# BMS_Schematic.net
KiCad netlist of a schematic drawn in Altium Designer
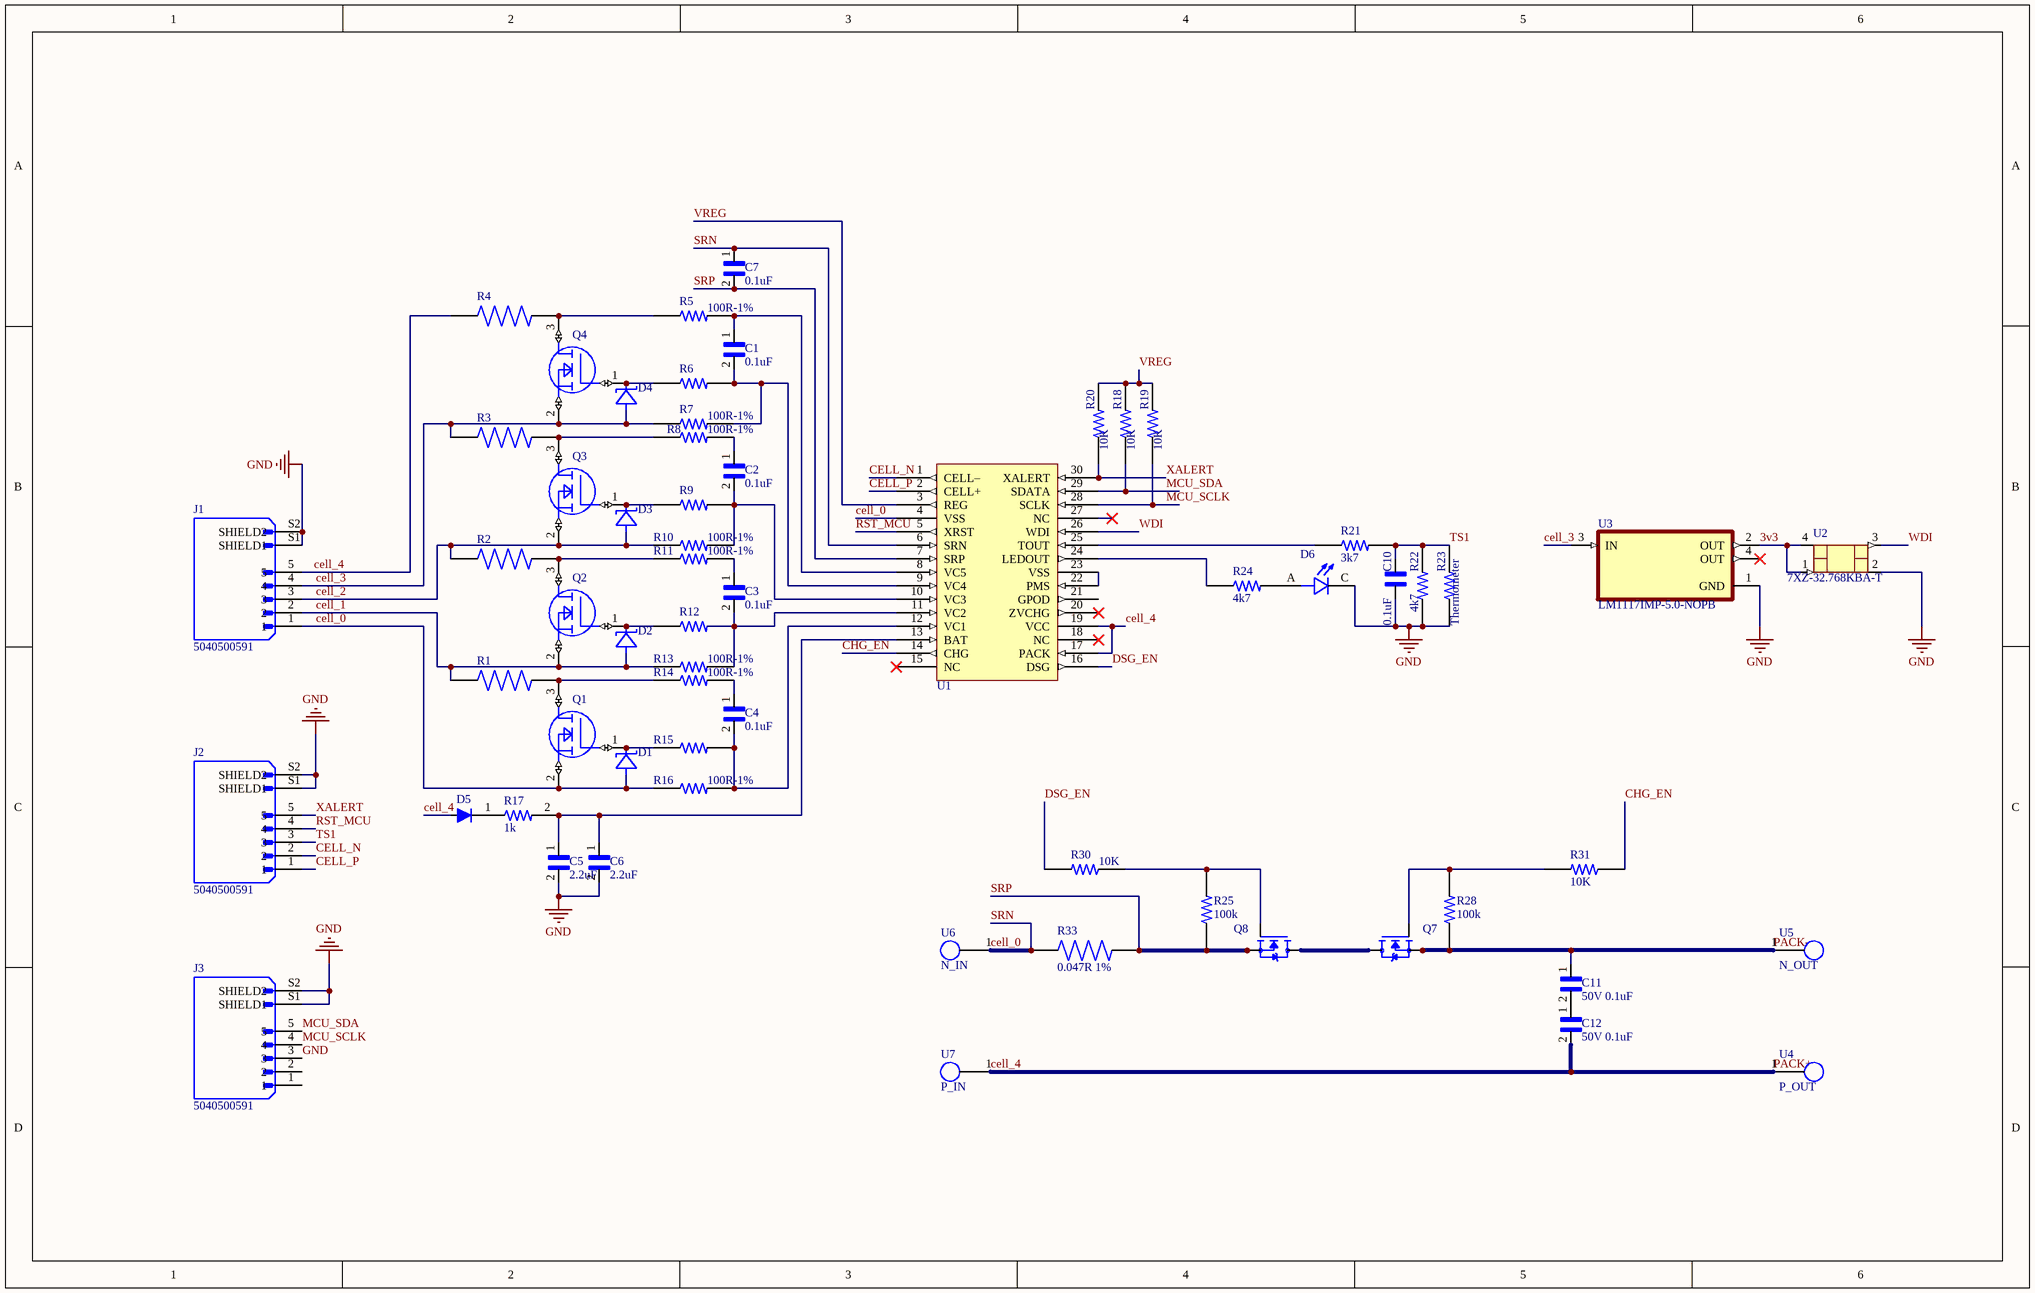
[diagram p0: BMS_Schematic.SchDoc]

(export (version "E")
  (design (tool "Eeschema 10.0.6"))
  (components
    (comp (ref "C1")
      (value "0.1uF")
      (footprint "cap_0603:CAPC1608X90")
      (description "CAP CER SMD")
      (fields (field (name "MP") "LD035C181JAB2A") (field (name "MF") "AVX"))
      (libsource (lib "cap_0603") (part "LD035C181JAB2A"))
    )
    (comp (ref "C2")
      (value "0.1uF")
      (footprint "CAPC1608X90")
      (description "CAP CER SMD")
      (fields (field (name "MP") "LD035C181JAB2A") (field (name "MF") "AVX"))
      (libsource (lib "LD035C181JAB2A") (part "LD035C181JAB2A"))
    )
    (comp (ref "C3")
      (value "0.1uF")
      (footprint "CAPC1608X90")
      (description "CAP CER SMD")
      (fields (field (name "MP") "LD035C181JAB2A") (field (name "MF") "AVX"))
      (libsource (lib "LD035C181JAB2A") (part "LD035C181JAB2A"))
    )
    (comp (ref "C4")
      (value "0.1uF")
      (footprint "CAPC1608X90")
      (description "CAP CER SMD")
      (fields (field (name "MP") "LD035C181JAB2A") (field (name "MF") "AVX"))
      (libsource (lib "LD035C181JAB2A") (part "LD035C181JAB2A"))
    )
    (comp (ref "C5")
      (value "2.2uF")
      (footprint "CAPC1608X90")
      (description "CAP CER SMD")
      (fields (field (name "MP") "LD035C181JAB2A") (field (name "MF") "AVX"))
      (libsource (lib "LD035C181JAB2A") (part "LD035C181JAB2A"))
    )
    (comp (ref "C6")
      (value "2.2uF")
      (footprint "CAPC1608X90")
      (description "CAP CER SMD")
      (fields (field (name "MP") "LD035C181JAB2A") (field (name "MF") "AVX"))
      (libsource (lib "LD035C181JAB2A") (part "LD035C181JAB2A"))
    )
    (comp (ref "C7")
      (value "0.1uF")
      (footprint "CAPC1608X90")
      (description "CAP CER SMD")
      (fields (field (name "MP") "LD035C181JAB2A") (field (name "MF") "AVX"))
      (libsource (lib "LD035C181JAB2A") (part "LD035C181JAB2A"))
    )
    (comp (ref "C10")
      (value "0.1uF")
      (footprint "CAPC1608X90")
      (description "CAP CER SMD")
      (fields (field (name "MP") "LD035C181JAB2A") (field (name "MF") "AVX"))
      (libsource (lib "") (part "LD035C181JAB2A_1"))
    )
    (comp (ref "C11")
      (value "50V 0.1uF")
      (footprint "CAPC1608X90")
      (description "CAP CER SMD")
      (fields (field (name "MP") "LD035C181JAB2A") (field (name "MF") "AVX"))
      (libsource (lib "LD035C181JAB2A") (part "LD035C181JAB2A"))
    )
    (comp (ref "C12")
      (value "50V 0.1uF")
      (footprint "CAPC1608X90")
      (description "CAP CER SMD")
      (fields (field (name "MP") "LD035C181JAB2A") (field (name "MF") "AVX"))
      (libsource (lib "LD035C181JAB2A") (part "LD035C181JAB2A"))
    )
    (comp (ref "D1")
      (value "MMSZ5232B+")
      (footprint "SOD123:SOD123")
      (description "Zener Diode 5.6V 500mW Â±5% Surface Mount SOD-123")
      (fields (field (name "MP") "MMSZ5232B") (field (name "MF") "ON Semiconductor"))
      (libsource (lib "MMSZ5232B+") (part "MMSZ5232B+"))
    )
    (comp (ref "D2")
      (value "MMSZ5232B+")
      (footprint "SOD123:SOD123")
      (description "Zener Diode 5.6V 500mW Â±5% Surface Mount SOD-123")
      (fields (field (name "MP") "MMSZ5232B") (field (name "MF") "ON Semiconductor"))
      (libsource (lib "MMSZ5232B+") (part "MMSZ5232B+"))
    )
    (comp (ref "D3")
      (value "MMSZ5232B+")
      (footprint "SOD123:SOD123")
      (description "Zener Diode 5.6V 500mW Â±5% Surface Mount SOD-123")
      (fields (field (name "MP") "MMSZ5232B") (field (name "MF") "ON Semiconductor"))
      (libsource (lib "MMSZ5232B+") (part "MMSZ5232B+"))
    )
    (comp (ref "D4")
      (value "MMSZ5232B+")
      (footprint "SOD123:SOD123")
      (description "Zener Diode 5.6V 500mW Â±5% Surface Mount SOD-123")
      (fields (field (name "MP") "MMSZ5232B") (field (name "MF") "ON Semiconductor"))
      (libsource (lib "MMSZ5232B+") (part "MMSZ5232B+"))
    )
    (comp (ref "D5")
      (value "MMSD4148T1G")
      (footprint "SnapEDApcb:SOD123")
      (description "DIODE GEN PURP 100V 200MA SOD123")
      (fields (field (name "MF") "ON Semiconductor") (field (name "MP") "MBR0520L"))
      (libsource (lib "SnapEDAsch") (part "MMSD4148T1G"))
    )
    (comp (ref "D6")
      (value "SML-D12U1WT86")
      (footprint "led_0603:LED_SML-D12Y1WT86")
      (description "Red 620nm LED Indication - Discrete 2.2V 0603 _1608 Metric_")
      (fields (field (name "MF") "Rohm"))
      (libsource (lib "led_0603") (part "SML-D12U1WT86"))
    )
    (comp (ref "J1")
      (value "5040500591")
      (footprint "MOLEX_5040500591:MOLEX_5040500591")
      (description "Connector Header Surface Mount, Right Angle 5 position 0.059 (1.50mm)")
      (fields (field (name "MF") "Molex"))
      (libsource (lib "5040500591") (part "5040500591"))
    )
    (comp (ref "J2")
      (value "5040500591")
      (footprint "MOLEX_5040500591:MOLEX_5040500591")
      (description "Connector Header Surface Mount, Right Angle 5 position 0.059 (1.50mm)")
      (fields (field (name "MF") "Molex"))
      (libsource (lib "5040500591") (part "5040500591"))
    )
    (comp (ref "J3")
      (value "5040500591")
      (footprint "MOLEX_5040500591:MOLEX_5040500591")
      (description "Connector Header Surface Mount, Right Angle 5 position 0.059 (1.50mm)")
      (fields (field (name "MF") "Molex"))
      (libsource (lib "5040500591") (part "5040500591"))
    )
    (comp (ref "Q1")
      (value "DMG2302UK-7")
      (footprint "SOT91P240X105-3N")
      (description "N-Channel 20 V 2.8A (Ta) 660mW (Ta) Surface Mount SOT-23-3")
      (fields (field (name "MF") "Diodes Inc."))
      (libsource (lib "DMG2302UK-7") (part "DMG2302UK-7"))
    )
    (comp (ref "Q2")
      (value "DMG2302UK-7")
      (footprint "SOT91P240X105-3N")
      (description "N-Channel 20 V 2.8A (Ta) 660mW (Ta) Surface Mount SOT-23-3")
      (fields (field (name "MF") "Diodes Inc."))
      (libsource (lib "DMG2302UK-7") (part "DMG2302UK-7"))
    )
    (comp (ref "Q3")
      (value "DMG2302UK-7")
      (footprint "SOT91P240X105-3N")
      (description "N-Channel 20 V 2.8A (Ta) 660mW (Ta) Surface Mount SOT-23-3")
      (fields (field (name "MF") "Diodes Inc."))
      (libsource (lib "DMG2302UK-7") (part "DMG2302UK-7"))
    )
    (comp (ref "Q4")
      (value "DMG2302UK-7")
      (footprint "SOT91P240X105-3N")
      (description "N-Channel 20 V 2.8A (Ta) 660mW (Ta) Surface Mount SOT-23-3")
      (fields (field (name "MF") "Diodes Inc."))
      (libsource (lib "DMG2302UK-7") (part "DMG2302UK-7"))
    )
    (comp (ref "Q7")
      (value "IPT60R028G7XTMA1")
      (footprint "MOSFET_8HSOF:TRANS_IPT60R028G7XTMA1")
      (fields
        (field (name "MF") "Infineon Technologies")
        (field (name "DIGI-KEY_PART_NUMBER") "IPT60R028G7XTMA1CT-ND")
      )
      (libsource (lib "MOSFET_8HSOF") (part "IPT60R028G7XTMA1"))
    )
    (comp (ref "Q8")
      (value "IPT60R028G7XTMA1")
      (footprint "MOSFET_8HSOF:TRANS_IPT60R028G7XTMA1")
      (fields
        (field (name "MF") "Infineon Technologies")
        (field (name "DIGI-KEY_PART_NUMBER") "IPT60R028G7XTMA1CT-ND")
      )
      (libsource (lib "MOSFET_8HSOF") (part "IPT60R028G7XTMA1"))
    )
    (comp (ref "R1")
      (value "ERJS1TJ561U")
      (footprint "RES_ERJS1TJ561U:RES_ERJS1TJ561U")
      (libsource (lib "ERJS1TJ561U") (part "ERJS1TJ561U"))
    )
    (comp (ref "R2")
      (value "ERJS1TJ561U")
      (footprint "RES_ERJS1TJ561U:RES_ERJS1TJ561U")
      (libsource (lib "ERJS1TJ561U") (part "ERJS1TJ561U"))
    )
    (comp (ref "R3")
      (value "ERJS1TJ561U")
      (footprint "RES_ERJS1TJ561U:RES_ERJS1TJ561U")
      (libsource (lib "ERJS1TJ561U") (part "ERJS1TJ561U"))
    )
    (comp (ref "R4")
      (value "ERJS1TJ561U")
      (footprint "RES_ERJS1TJ561U:RES_ERJS1TJ561U")
      (libsource (lib "ERJS1TJ561U") (part "ERJS1TJ561U"))
    )
    (comp (ref "R5")
      (value "100R-1%")
      (footprint "RESC1608X50N:RESC1608X50N")
      (description "CPF 0603 10K 0.1% 25PPM 1K RL")
      (fields (field (name "MP") "8-1676481-6"))
      (libsource (lib "8-1676481-6") (part "8-1676481-6"))
    )
    (comp (ref "R6")
      (value "8-1676481-6")
      (footprint "RESC1608X50N:RESC1608X50N")
      (description "CPF 0603 10K 0.1% 25PPM 1K RL")
      (libsource (lib "8-1676481-6") (part "8-1676481-6"))
    )
    (comp (ref "R7")
      (value "100R-1%")
      (footprint "RESC1608X50N:RESC1608X50N")
      (description "CPF 0603 10K 0.1% 25PPM 1K RL")
      (fields (field (name "MP") "8-1676481-6"))
      (libsource (lib "8-1676481-6") (part "8-1676481-6"))
    )
    (comp (ref "R8")
      (value "100R-1%")
      (footprint "RESC1608X50N:RESC1608X50N")
      (description "CPF 0603 10K 0.1% 25PPM 1K RL")
      (fields (field (name "MP") "8-1676481-6"))
      (libsource (lib "8-1676481-6") (part "8-1676481-6"))
    )
    (comp (ref "R9")
      (value "8-1676481-6")
      (footprint "RESC1608X50N:RESC1608X50N")
      (description "CPF 0603 10K 0.1% 25PPM 1K RL")
      (libsource (lib "8-1676481-6") (part "8-1676481-6"))
    )
    (comp (ref "R10")
      (value "100R-1%")
      (footprint "RESC1608X50N:RESC1608X50N")
      (description "CPF 0603 10K 0.1% 25PPM 1K RL")
      (fields (field (name "MP") "8-1676481-6"))
      (libsource (lib "8-1676481-6") (part "8-1676481-6"))
    )
    (comp (ref "R11")
      (value "100R-1%")
      (footprint "RESC1608X50N:RESC1608X50N")
      (description "CPF 0603 10K 0.1% 25PPM 1K RL")
      (fields (field (name "MP") "8-1676481-6"))
      (libsource (lib "8-1676481-6") (part "8-1676481-6"))
    )
    (comp (ref "R12")
      (value "8-1676481-6")
      (footprint "RESC1608X50N:RESC1608X50N")
      (description "CPF 0603 10K 0.1% 25PPM 1K RL")
      (libsource (lib "8-1676481-6") (part "8-1676481-6"))
    )
    (comp (ref "R13")
      (value "100R-1%")
      (footprint "RESC1608X50N:RESC1608X50N")
      (description "CPF 0603 10K 0.1% 25PPM 1K RL")
      (fields (field (name "MP") "8-1676481-6"))
      (libsource (lib "8-1676481-6") (part "8-1676481-6"))
    )
    (comp (ref "R14")
      (value "100R-1%")
      (footprint "RESC1608X50N:RESC1608X50N")
      (description "CPF 0603 10K 0.1% 25PPM 1K RL")
      (fields (field (name "MP") "8-1676481-6"))
      (libsource (lib "8-1676481-6") (part "8-1676481-6"))
    )
    (comp (ref "R15")
      (value "8-1676481-6")
      (footprint "RESC1608X50N:RESC1608X50N")
      (description "CPF 0603 10K 0.1% 25PPM 1K RL")
      (libsource (lib "8-1676481-6") (part "8-1676481-6"))
    )
    (comp (ref "R16")
      (value "100R-1%")
      (footprint "RESC1608X50N:RESC1608X50N")
      (description "CPF 0603 10K 0.1% 25PPM 1K RL")
      (fields (field (name "MP") "8-1676481-6"))
      (libsource (lib "8-1676481-6") (part "8-1676481-6"))
    )
    (comp (ref "R17")
      (value "1k")
      (footprint "RESC1608X50N")
      (description "CPF 0603 30K 0.1% 25PPM 1K RL")
      (fields (field (name "MP") "8-1676481-6"))
      (libsource (lib "") (part "8-1676481-6_1"))
    )
    (comp (ref "R18")
      (value "10K")
      (footprint "RESC1608X50N:RESC1608X50N")
      (description "CPF 0603 10K 0.1% 25PPM 1K RL")
      (fields (field (name "MP") "8-1676481-6"))
      (libsource (lib "8-1676481-6") (part "8-1676481-6"))
    )
    (comp (ref "R19")
      (value "10K")
      (footprint "RESC1608X50N:RESC1608X50N")
      (description "CPF 0603 10K 0.1% 25PPM 1K RL")
      (fields (field (name "MP") "8-1676481-6"))
      (libsource (lib "8-1676481-6") (part "8-1676481-6"))
    )
    (comp (ref "R20")
      (value "10K")
      (footprint "RESC1608X50N:RESC1608X50N")
      (description "CPF 0603 10K 0.1% 25PPM 1K RL")
      (fields (field (name "MP") "8-1676481-6"))
      (libsource (lib "8-1676481-6") (part "8-1676481-6"))
    )
    (comp (ref "R21")
      (value "3k7")
      (footprint "RESC1608X50N:RESC1608X50N")
      (description "CPF 0603 10K 0.1% 25PPM 1K RL")
      (fields (field (name "MP") "8-1676481-6"))
      (libsource (lib "8-1676481-6") (part "8-1676481-6"))
    )
    (comp (ref "R22")
      (value "4k7")
      (footprint "RESC1608X50N:RESC1608X50N")
      (description "CPF 0603 10K 0.1% 25PPM 1K RL")
      (fields (field (name "MP") "8-1676481-6"))
      (libsource (lib "8-1676481-6") (part "8-1676481-6"))
    )
    (comp (ref "R23")
      (value "Thermometer")
      (footprint "RESC1608X50N:RESC1608X50N")
      (description "CPF 0603 10K 0.1% 25PPM 1K RL")
      (fields (field (name "MP") "8-1676481-6"))
      (libsource (lib "8-1676481-6") (part "8-1676481-6"))
    )
    (comp (ref "R24")
      (value "4k7")
      (footprint "RESC1608X50N:RESC1608X50N")
      (description "CPF 0603 10K 0.1% 25PPM 1K RL")
      (fields (field (name "MP") "8-1676481-6"))
      (libsource (lib "8-1676481-6") (part "8-1676481-6"))
    )
    (comp (ref "R25")
      (value "100k")
      (footprint "RESC1608X50N:RESC1608X50N")
      (description "CPF 0603 10K 0.1% 25PPM 1K RL")
      (fields (field (name "MP") "8-1676481-6"))
      (libsource (lib "8-1676481-6") (part "8-1676481-6"))
    )
    (comp (ref "R28")
      (value "100k")
      (footprint "RESC1608X50N:RESC1608X50N")
      (description "CPF 0603 10K 0.1% 25PPM 1K RL")
      (fields (field (name "MP") "8-1676481-6"))
      (libsource (lib "8-1676481-6") (part "8-1676481-6"))
    )
    (comp (ref "R30")
      (value "10K")
      (footprint "RESC1608X50N:RESC1608X50N")
      (description "CPF 0603 10K 0.1% 25PPM 1K RL")
      (fields (field (name "MP") "8-1676481-6"))
      (libsource (lib "8-1676481-6") (part "8-1676481-6"))
    )
    (comp (ref "R31")
      (value "10K")
      (footprint "RESC1608X50N:RESC1608X50N")
      (description "CPF 0603 10K 0.1% 25PPM 1K RL")
      (fields (field (name "MP") "8-1676481-6"))
      (libsource (lib "8-1676481-6") (part "8-1676481-6"))
    )
    (comp (ref "R33")
      (value "0.047R 1%")
      (footprint "RES_ERJS1TJ561U:RES_ERJS1TJ561U")
      (fields (field (name "MP") "ERJS1TJ561U"))
      (libsource (lib "ERJS1TJ561U") (part "ERJS1TJ561U"))
    )
    (comp (ref "U1")
      (value "BQ29330")
      (footprint "SOP50P640X120-30N")
      (libsource (lib "BQ29330DBT") (part "BQ29330"))
    )
    (comp (ref "U2")
      (value "7XZ-32.768KBA-T")
      (footprint "oscillator:OSCCILATOR")
      (description "Oscillator 32.768 Khz")
      (libsource (lib "oscillator") (part "7XZ-32.768KBA-T"))
    )
    (comp (ref "U3")
      (value "LM1117IMP-5.0-NOPB")
      (footprint "SOT230P700X180-4N:SOT230P700X180-4N")
      (fields (field (name "MF") "Texas Instruments") (field (name "MP") "LM1117IMP50"))
      (libsource (lib "LM1117IMP-5.0-NOPB") (part "LM1117IMP-5.0-NOPB"))
    )
    (comp (ref "U4")
      (value "P_OUT")
      (footprint "battery_socket:PCBComponent_1")
      (description "Soldering part")
      (libsource (lib "battery_socket") (part "battery_socket"))
    )
    (comp (ref "U5")
      (value "N_OUT")
      (footprint "battery_socket:PCBComponent_1")
      (description "Soldering part")
      (libsource (lib "battery_socket") (part "battery_socket"))
    )
    (comp (ref "U6")
      (value "N_IN")
      (footprint "battery_socket:PCBComponent_1")
      (description "Soldering part")
      (libsource (lib "battery_socket") (part "battery_socket"))
    )
    (comp (ref "U7")
      (value "P_IN")
      (footprint "battery_socket:PCBComponent_1")
      (description "Soldering part")
      (libsource (lib "battery_socket") (part "battery_socket"))
    )
  )
  (nets
    (net (code "1") (name "/3v3") (class "Default")
      (node (ref "U2") (pin "1") (pinfunction "ENA_1") (pintype "input"))
      (node (ref "U2") (pin "4") (pinfunction "VDD_4") (pintype "power_in"))
      (node (ref "U3") (pin "2") (pinfunction "OUT_2") (pintype "output"))
    )
    (net (code "2") (name "/CELL_N") (class "Default")
      (node (ref "J2") (pin "2") (pinfunction "2_2") (pintype "passive"))
      (node (ref "U1") (pin "1") (pinfunction "CELL–_1") (pintype "output"))
    )
    (net (code "3") (name "/CELL_P") (class "Default")
      (node (ref "J2") (pin "1") (pinfunction "1_1") (pintype "passive"))
      (node (ref "U1") (pin "2") (pinfunction "CELL+_2") (pintype "output"))
    )
    (net (code "4") (name "/CHG_EN") (class "Default")
      (node (ref "R31") (pin "1") (pinfunction "1_1") (pintype "passive"))
      (node (ref "U1") (pin "14") (pinfunction "CHG_14") (pintype "output"))
    )
    (net (code "5") (name "/DSG_EN") (class "Default")
      (node (ref "R30") (pin "2") (pinfunction "2_2") (pintype "passive"))
      (node (ref "U1") (pin "16") (pinfunction "DSG_16") (pintype "output"))
    )
    (net (code "6") (name "/MCU_SCLK") (class "Default")
      (node (ref "J3") (pin "4") (pinfunction "4_4") (pintype "passive"))
      (node (ref "R19") (pin "1") (pinfunction "1_1") (pintype "passive"))
      (node (ref "U1") (pin "28") (pinfunction "SCLK_28") (pintype "input"))
    )
    (net (code "7") (name "/MCU_SDA") (class "Default")
      (node (ref "J3") (pin "5") (pinfunction "5_5") (pintype "passive"))
      (node (ref "R18") (pin "1") (pinfunction "1_1") (pintype "passive"))
      (node (ref "U1") (pin "29") (pinfunction "SDATA_29") (pintype "input"))
    )
    (net (code "8") (name "/PACK+") (class "Default")
      (node (ref "C12") (pin "2") (pinfunction "2_2") (pintype "passive"))
      (node (ref "D5") (pin "A") (pinfunction "A_A") (pintype "passive"))
      (node (ref "J1") (pin "5") (pinfunction "5_5") (pintype "passive"))
      (node (ref "R4") (pin "1") (pinfunction "1_1") (pintype "passive"))
      (node (ref "U1") (pin "17") (pinfunction "PACK_17") (pintype "input"))
      (node (ref "U1") (pin "19") (pinfunction "VCC_19") (pintype "power_in"))
      (node (ref "U4") (pin "1") (pintype "power_in"))
      (node (ref "U7") (pin "1") (pintype "power_in"))
    )
    (net (code "9") (name "/PACK-") (class "Default")
      (node (ref "C11") (pin "1") (pinfunction "1_1") (pintype "passive"))
      (node (ref "Q7") (pin "2") (pinfunction "SOURCE_2") (pintype "passive"))
      (node (ref "Q7") (pin "3") (pinfunction "SOURCE_3") (pintype "passive"))
      (node (ref "Q7") (pin "4") (pinfunction "SOURCE_4") (pintype "passive"))
      (node (ref "Q7") (pin "5") (pinfunction "SOURCE_5") (pintype "passive"))
      (node (ref "Q7") (pin "6") (pinfunction "SOURCE_6") (pintype "passive"))
      (node (ref "Q7") (pin "7") (pinfunction "SOURCE_7") (pintype "passive"))
      (node (ref "Q7") (pin "8") (pinfunction "SOURCE_8") (pintype "passive"))
      (node (ref "R28") (pin "1") (pinfunction "1_1") (pintype "passive"))
      (node (ref "U5") (pin "1") (pintype "power_in"))
    )
    (net (code "10") (name "/RST_MCU") (class "Default")
      (node (ref "J2") (pin "4") (pinfunction "4_4") (pintype "passive"))
      (node (ref "U1") (pin "5") (pinfunction "XRST_5") (pintype "output"))
    )
    (net (code "11") (name "/SRN") (class "Default")
      (node (ref "C7") (pin "1") (pinfunction "1_1") (pintype "passive"))
      (node (ref "D1") (pin "2") (pinfunction "A_2") (pintype "passive"))
      (node (ref "J1") (pin "1") (pinfunction "1_1") (pintype "passive"))
      (node (ref "Q1") (pin "2") (pinfunction "S_2") (pintype "bidirectional"))
      (node (ref "R16") (pin "1") (pinfunction "1_1") (pintype "passive"))
      (node (ref "R33") (pin "1") (pinfunction "1_1") (pintype "passive"))
      (node (ref "U1") (pin "4") (pinfunction "VSS_4") (pintype "power_in"))
      (node (ref "U1") (pin "6") (pinfunction "SRN_6") (pintype "input"))
      (node (ref "U6") (pin "1") (pintype "power_in"))
    )
    (net (code "12") (name "/SRP") (class "Default")
      (node (ref "C7") (pin "2") (pinfunction "2_2") (pintype "passive"))
      (node (ref "Q8") (pin "2") (pinfunction "SOURCE_2") (pintype "passive"))
      (node (ref "Q8") (pin "3") (pinfunction "SOURCE_3") (pintype "passive"))
      (node (ref "Q8") (pin "4") (pinfunction "SOURCE_4") (pintype "passive"))
      (node (ref "Q8") (pin "5") (pinfunction "SOURCE_5") (pintype "passive"))
      (node (ref "Q8") (pin "6") (pinfunction "SOURCE_6") (pintype "passive"))
      (node (ref "Q8") (pin "7") (pinfunction "SOURCE_7") (pintype "passive"))
      (node (ref "Q8") (pin "8") (pinfunction "SOURCE_8") (pintype "passive"))
      (node (ref "R25") (pin "1") (pinfunction "1_1") (pintype "passive"))
      (node (ref "R33") (pin "2") (pinfunction "2_2") (pintype "passive"))
      (node (ref "U1") (pin "7") (pinfunction "SRP_7") (pintype "input"))
    )
    (net (code "13") (name "/TS1") (class "Default")
      (node (ref "C10") (pin "1") (pinfunction "1_1") (pintype "passive"))
      (node (ref "J2") (pin "3") (pinfunction "3_3") (pintype "passive"))
      (node (ref "R21") (pin "2") (pinfunction "2_2") (pintype "passive"))
      (node (ref "R22") (pin "2") (pinfunction "2_2") (pintype "passive"))
      (node (ref "R23") (pin "2") (pinfunction "2_2") (pintype "passive"))
    )
    (net (code "14") (name "/VREG") (class "Default")
      (node (ref "R18") (pin "2") (pinfunction "2_2") (pintype "passive"))
      (node (ref "R19") (pin "2") (pinfunction "2_2") (pintype "passive"))
      (node (ref "R20") (pin "2") (pinfunction "2_2") (pintype "passive"))
      (node (ref "U1") (pin "3") (pinfunction "REG_3") (pintype "output"))
    )
    (net (code "15") (name "/WDI") (class "Default")
      (node (ref "U1") (pin "26") (pinfunction "WDI_26") (pintype "input"))
      (node (ref "U2") (pin "3") (pinfunction "OUT_3") (pintype "output"))
    )
    (net (code "16") (name "/XALERT") (class "Default")
      (node (ref "J2") (pin "5") (pinfunction "5_5") (pintype "passive"))
      (node (ref "R20") (pin "1") (pinfunction "1_1") (pintype "passive"))
      (node (ref "U1") (pin "30") (pinfunction "XALERT_30") (pintype "input"))
    )
    (net (code "17") (name "/cell_1") (class "Default")
      (node (ref "D2") (pin "2") (pinfunction "A_2") (pintype "passive"))
      (node (ref "J1") (pin "2") (pinfunction "2_2") (pintype "passive"))
      (node (ref "Q2") (pin "2") (pinfunction "S_2") (pintype "bidirectional"))
      (node (ref "R1") (pin "1") (pinfunction "1_1") (pintype "passive"))
      (node (ref "R13") (pin "1") (pinfunction "1_1") (pintype "passive"))
    )
    (net (code "18") (name "/cell_2") (class "Default")
      (node (ref "D3") (pin "2") (pinfunction "A_2") (pintype "passive"))
      (node (ref "J1") (pin "3") (pinfunction "3_3") (pintype "passive"))
      (node (ref "Q3") (pin "2") (pinfunction "S_2") (pintype "bidirectional"))
      (node (ref "R10") (pin "1") (pinfunction "1_1") (pintype "passive"))
      (node (ref "R2") (pin "1") (pinfunction "1_1") (pintype "passive"))
    )
    (net (code "19") (name "/cell_3") (class "Default")
      (node (ref "D4") (pin "2") (pinfunction "A_2") (pintype "passive"))
      (node (ref "J1") (pin "4") (pinfunction "4_4") (pintype "passive"))
      (node (ref "Q4") (pin "2") (pinfunction "S_2") (pintype "bidirectional"))
      (node (ref "R3") (pin "1") (pinfunction "1_1") (pintype "passive"))
      (node (ref "R7") (pin "1") (pinfunction "1_1") (pintype "passive"))
      (node (ref "U3") (pin "3") (pinfunction "IN_3") (pintype "input"))
    )
    (net (code "20") (name "GND") (class "Default")
      (node (ref "C10") (pin "2") (pinfunction "2_2") (pintype "passive"))
      (node (ref "C5") (pin "2") (pinfunction "2_2") (pintype "passive"))
      (node (ref "C6") (pin "2") (pinfunction "2_2") (pintype "passive"))
      (node (ref "D6") (pin "C") (pinfunction "C_C") (pintype "passive"))
      (node (ref "J1") (pin "S1") (pinfunction "SHIELD1_S1") (pintype "passive"))
      (node (ref "J1") (pin "S2") (pinfunction "SHIELD2_S2") (pintype "passive"))
      (node (ref "J2") (pin "S1") (pinfunction "SHIELD1_S1") (pintype "passive"))
      (node (ref "J2") (pin "S2") (pinfunction "SHIELD2_S2") (pintype "passive"))
      (node (ref "J3") (pin "3") (pinfunction "3_3") (pintype "passive"))
      (node (ref "J3") (pin "S1") (pinfunction "SHIELD1_S1") (pintype "passive"))
      (node (ref "J3") (pin "S2") (pinfunction "SHIELD2_S2") (pintype "passive"))
      (node (ref "R22") (pin "1") (pinfunction "1_1") (pintype "passive"))
      (node (ref "R23") (pin "1") (pinfunction "1_1") (pintype "passive"))
      (node (ref "U2") (pin "2") (pinfunction "GND_2") (pintype "power_in"))
      (node (ref "U3") (pin "1") (pinfunction "GND_1") (pintype "power_in"))
    )
    (net (code "21") (name "Net-(C2-Pad1)") (class "Default")
      (node (ref "C2") (pin "1") (pinfunction "1_1") (pintype "passive"))
      (node (ref "R8") (pin "2") (pinfunction "2_2") (pintype "passive"))
    )
    (net (code "22") (name "Net-(C3-Pad1)") (class "Default")
      (node (ref "C3") (pin "1") (pinfunction "1_1") (pintype "passive"))
      (node (ref "R11") (pin "2") (pinfunction "2_2") (pintype "passive"))
    )
    (net (code "23") (name "Net-(C4-Pad1)") (class "Default")
      (node (ref "C4") (pin "1") (pinfunction "1_1") (pintype "passive"))
      (node (ref "R14") (pin "2") (pinfunction "2_2") (pintype "passive"))
    )
    (net (code "24") (name "Net-(C11-Pad2)") (class "Default")
      (node (ref "C11") (pin "2") (pinfunction "2_2") (pintype "passive"))
      (node (ref "C12") (pin "1") (pinfunction "1_1") (pintype "passive"))
    )
    (net (code "25") (name "Net-(D1-C)") (class "Default")
      (node (ref "D1") (pin "1") (pinfunction "C_1") (pintype "passive"))
      (node (ref "Q1") (pin "1") (pinfunction "G_1") (pintype "bidirectional"))
      (node (ref "R15") (pin "1") (pinfunction "1_1") (pintype "passive"))
    )
    (net (code "26") (name "Net-(D2-C)") (class "Default")
      (node (ref "D2") (pin "1") (pinfunction "C_1") (pintype "passive"))
      (node (ref "Q2") (pin "1") (pinfunction "G_1") (pintype "bidirectional"))
      (node (ref "R12") (pin "1") (pinfunction "1_1") (pintype "passive"))
    )
    (net (code "27") (name "Net-(D3-C)") (class "Default")
      (node (ref "D3") (pin "1") (pinfunction "C_1") (pintype "passive"))
      (node (ref "Q3") (pin "1") (pinfunction "G_1") (pintype "bidirectional"))
      (node (ref "R9") (pin "1") (pinfunction "1_1") (pintype "passive"))
    )
    (net (code "28") (name "Net-(D4-C)") (class "Default")
      (node (ref "D4") (pin "1") (pinfunction "C_1") (pintype "passive"))
      (node (ref "Q4") (pin "1") (pinfunction "G_1") (pintype "bidirectional"))
      (node (ref "R6") (pin "1") (pinfunction "1_1") (pintype "passive"))
    )
    (net (code "29") (name "Net-(D5-PadC)") (class "Default")
      (node (ref "D5") (pin "C") (pinfunction "C_C") (pintype "passive"))
      (node (ref "R17") (pin "1") (pinfunction "1_1") (pintype "passive"))
    )
    (net (code "30") (name "Net-(D6-PadA)") (class "Default")
      (node (ref "D6") (pin "A") (pinfunction "A_A") (pintype "passive"))
      (node (ref "R24") (pin "2") (pinfunction "2_2") (pintype "passive"))
    )
    (net (code "31") (name "Net-(Q1-D)") (class "Default")
      (node (ref "Q1") (pin "3") (pinfunction "D_3") (pintype "bidirectional"))
      (node (ref "R1") (pin "2") (pinfunction "2_2") (pintype "passive"))
      (node (ref "R14") (pin "1") (pinfunction "1_1") (pintype "passive"))
    )
    (net (code "32") (name "Net-(Q2-D)") (class "Default")
      (node (ref "Q2") (pin "3") (pinfunction "D_3") (pintype "bidirectional"))
      (node (ref "R11") (pin "1") (pinfunction "1_1") (pintype "passive"))
      (node (ref "R2") (pin "2") (pinfunction "2_2") (pintype "passive"))
    )
    (net (code "33") (name "Net-(Q3-D)") (class "Default")
      (node (ref "Q3") (pin "3") (pinfunction "D_3") (pintype "bidirectional"))
      (node (ref "R3") (pin "2") (pinfunction "2_2") (pintype "passive"))
      (node (ref "R8") (pin "1") (pinfunction "1_1") (pintype "passive"))
    )
    (net (code "34") (name "Net-(Q4-D)") (class "Default")
      (node (ref "Q4") (pin "3") (pinfunction "D_3") (pintype "bidirectional"))
      (node (ref "R4") (pin "2") (pinfunction "2_2") (pintype "passive"))
      (node (ref "R5") (pin "1") (pinfunction "1_1") (pintype "passive"))
    )
    (net (code "35") (name "Net-(Q7-DRAIN)") (class "Default")
      (node (ref "Q7") (pin "9") (pinfunction "DRAIN_9") (pintype "passive"))
      (node (ref "Q8") (pin "9") (pinfunction "DRAIN_9") (pintype "passive"))
    )
    (net (code "36") (name "Net-(Q7-GATE)") (class "Default")
      (node (ref "Q7") (pin "1") (pinfunction "GATE_1") (pintype "passive"))
      (node (ref "R28") (pin "2") (pinfunction "2_2") (pintype "passive"))
      (node (ref "R31") (pin "2") (pinfunction "2_2") (pintype "passive"))
    )
    (net (code "37") (name "Net-(Q8-GATE)") (class "Default")
      (node (ref "Q8") (pin "1") (pinfunction "GATE_1") (pintype "passive"))
      (node (ref "R25") (pin "2") (pinfunction "2_2") (pintype "passive"))
      (node (ref "R30") (pin "1") (pinfunction "1_1") (pintype "passive"))
    )
    (net (code "38") (name "Net-(U1-BAT)") (class "Default")
      (node (ref "C5") (pin "1") (pinfunction "1_1") (pintype "passive"))
      (node (ref "C6") (pin "1") (pinfunction "1_1") (pintype "passive"))
      (node (ref "R17") (pin "2") (pinfunction "2_2") (pintype "passive"))
      (node (ref "U1") (pin "13") (pinfunction "BAT_13") (pintype "input"))
    )
    (net (code "39") (name "Net-(U1-LEDOUT)") (class "Default")
      (node (ref "R24") (pin "1") (pinfunction "1_1") (pintype "passive"))
      (node (ref "U1") (pin "24") (pinfunction "LEDOUT_24") (pintype "output"))
    )
    (net (code "40") (name "Net-(U1-PMS)") (class "Default")
      (node (ref "U1") (pin "22") (pinfunction "PMS_22") (pintype "input"))
      (node (ref "U1") (pin "23") (pinfunction "VSS_23") (pintype "power_in"))
    )
    (net (code "41") (name "Net-(U1-TOUT)") (class "Default")
      (node (ref "R21") (pin "1") (pinfunction "1_1") (pintype "passive"))
      (node (ref "U1") (pin "25") (pinfunction "TOUT_25") (pintype "input"))
    )
    (net (code "42") (name "Net-(U1-VC1)") (class "Default")
      (node (ref "C4") (pin "2") (pinfunction "2_2") (pintype "passive"))
      (node (ref "R15") (pin "2") (pinfunction "2_2") (pintype "passive"))
      (node (ref "R16") (pin "2") (pinfunction "2_2") (pintype "passive"))
      (node (ref "U1") (pin "12") (pinfunction "VC1_12") (pintype "input"))
    )
    (net (code "43") (name "Net-(U1-VC2)") (class "Default")
      (node (ref "C3") (pin "2") (pinfunction "2_2") (pintype "passive"))
      (node (ref "R12") (pin "2") (pinfunction "2_2") (pintype "passive"))
      (node (ref "R13") (pin "2") (pinfunction "2_2") (pintype "passive"))
      (node (ref "U1") (pin "11") (pinfunction "VC2_11") (pintype "input"))
    )
    (net (code "44") (name "Net-(U1-VC3)") (class "Default")
      (node (ref "C2") (pin "2") (pinfunction "2_2") (pintype "passive"))
      (node (ref "R10") (pin "2") (pinfunction "2_2") (pintype "passive"))
      (node (ref "R9") (pin "2") (pinfunction "2_2") (pintype "passive"))
      (node (ref "U1") (pin "10") (pinfunction "VC3_10") (pintype "input"))
    )
    (net (code "45") (name "Net-(U1-VC4)") (class "Default")
      (node (ref "C1") (pin "2") (pinfunction "2_2") (pintype "passive"))
      (node (ref "R6") (pin "2") (pinfunction "2_2") (pintype "passive"))
      (node (ref "R7") (pin "2") (pinfunction "2_2") (pintype "passive"))
      (node (ref "U1") (pin "9") (pinfunction "VC4_9") (pintype "input"))
    )
    (net (code "46") (name "Net-(U1-VC5)") (class "Default")
      (node (ref "C1") (pin "1") (pinfunction "1_1") (pintype "passive"))
      (node (ref "R5") (pin "2") (pinfunction "2_2") (pintype "passive"))
      (node (ref "U1") (pin "8") (pinfunction "VC5_8") (pintype "input"))
    )
    (net (code "47") (name "unconnected-(J3-Pad1)") (class "Default")
      (node (ref "J3") (pin "1") (pinfunction "1_1") (pintype "passive"))
    )
    (net (code "48") (name "unconnected-(J3-Pad2)") (class "Default")
      (node (ref "J3") (pin "2") (pinfunction "2_2") (pintype "passive"))
    )
    (net (code "49") (name "unconnected-(U1-GPOD-Pad21)") (class "Default")
      (node (ref "U1") (pin "21") (pinfunction "GPOD_21") (pintype "output"))
    )
    (net (code "50") (name "unconnected-(U1-NC-Pad15)") (class "Default")
      (node (ref "U1") (pin "15") (pinfunction "NC_15") (pintype "passive+no_connect"))
    )
    (net (code "51") (name "unconnected-(U1-NC-Pad18)") (class "Default")
      (node (ref "U1") (pin "18") (pinfunction "NC_18") (pintype "passive+no_connect"))
    )
    (net (code "52") (name "unconnected-(U1-NC-Pad27)") (class "Default")
      (node (ref "U1") (pin "27") (pinfunction "NC_27") (pintype "passive+no_connect"))
    )
    (net (code "53") (name "unconnected-(U1-ZVCHG-Pad20)") (class "Default")
      (node (ref "U1") (pin "20") (pinfunction "ZVCHG_20") (pintype "output+no_connect"))
    )
    (net (code "54") (name "unconnected-(U3-OUT-Pad4)") (class "Default")
      (node (ref "U3") (pin "4") (pinfunction "OUT_4") (pintype "output+no_connect"))
    )
  )
)
